# ASCII_Keyboard.net
KiCad netlist of a schematic drawn in Altium Designer
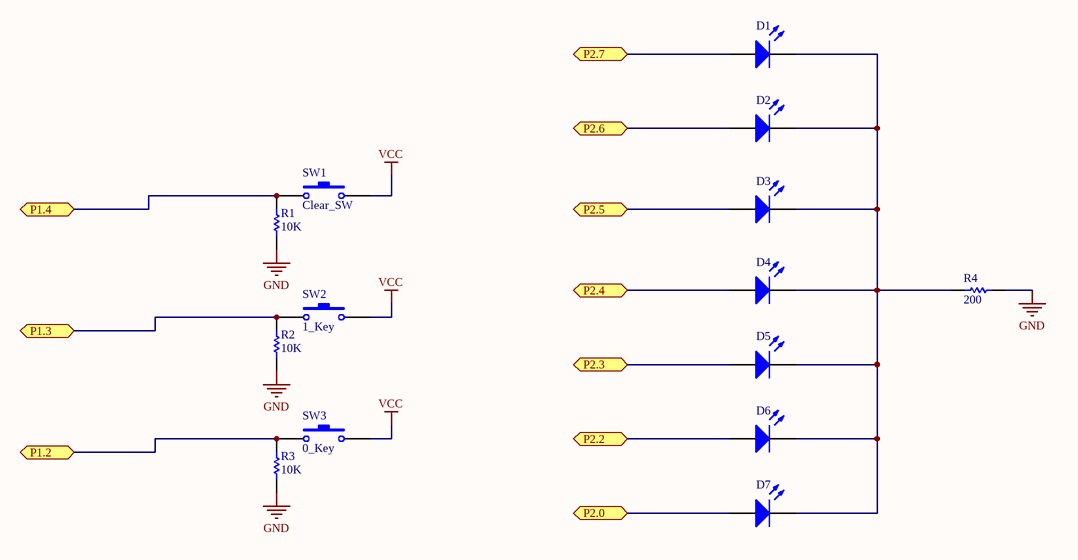
[diagram p0: ASCII_Keyboard.SchDoc]

(export (version "E")
  (design (tool "Eeschema 10.0.6"))
  (components
    (comp (ref "D1")
      (value "LED0")
      (footprint "LED-0")
      (description "Typical INFRARED GaAs LED")
      (fields (field (name "PUBLISHER") "Altium Limited"))
      (libsource (lib "Miscellaneous Devices") (part "LED0"))
    )
    (comp (ref "D2")
      (value "LED0")
      (footprint "LED-0")
      (description "Typical INFRARED GaAs LED")
      (fields (field (name "PUBLISHER") "Altium Limited"))
      (libsource (lib "Miscellaneous Devices") (part "LED0"))
    )
    (comp (ref "D3")
      (value "LED0")
      (footprint "LED-0")
      (description "Typical INFRARED GaAs LED")
      (fields (field (name "PUBLISHER") "Altium Limited"))
      (libsource (lib "Miscellaneous Devices") (part "LED0"))
    )
    (comp (ref "D4")
      (value "LED0")
      (footprint "LED-0")
      (description "Typical INFRARED GaAs LED")
      (fields (field (name "PUBLISHER") "Altium Limited"))
      (libsource (lib "Miscellaneous Devices") (part "LED0"))
    )
    (comp (ref "D5")
      (value "LED0")
      (footprint "LED-0")
      (description "Typical INFRARED GaAs LED")
      (fields (field (name "PUBLISHER") "Altium Limited"))
      (libsource (lib "Miscellaneous Devices") (part "LED0"))
    )
    (comp (ref "D6")
      (value "LED0")
      (footprint "LED-0")
      (description "Typical INFRARED GaAs LED")
      (fields (field (name "PUBLISHER") "Altium Limited"))
      (libsource (lib "Miscellaneous Devices") (part "LED0"))
    )
    (comp (ref "D7")
      (value "LED0")
      (footprint "LED-0")
      (description "Typical INFRARED GaAs LED")
      (fields (field (name "PUBLISHER") "Altium Limited"))
      (libsource (lib "Miscellaneous Devices") (part "LED0"))
    )
    (comp (ref "R1")
      (value "10K")
      (footprint "AXIAL-0.3")
      (description "Resistor")
      (fields (field (name "Comment") "Res1") (field (name "PUBLISHER") "Altium Limited"))
      (libsource (lib "Miscellaneous Devices") (part "Res1"))
    )
    (comp (ref "R2")
      (value "10K")
      (footprint "AXIAL-0.3")
      (description "Resistor")
      (fields (field (name "Comment") "Res1") (field (name "PUBLISHER") "Altium Limited"))
      (libsource (lib "Miscellaneous Devices") (part "Res1"))
    )
    (comp (ref "R3")
      (value "10K")
      (footprint "AXIAL-0.3")
      (description "Resistor")
      (fields (field (name "Comment") "Res1") (field (name "PUBLISHER") "Altium Limited"))
      (libsource (lib "Miscellaneous Devices") (part "Res1"))
    )
    (comp (ref "R4")
      (value "200")
      (footprint "AXIAL-0.3")
      (description "Resistor")
      (fields (field (name "Comment") "Res1") (field (name "PUBLISHER") "Altium Limited"))
      (libsource (lib "Miscellaneous Devices") (part "Res1"))
    )
    (comp (ref "SW1")
      (value "Clear_SW")
      (footprint "SPST-2")
      (description "Switch")
      (fields (field (name "PUBLISHER") "Altium Limited"))
      (libsource (lib "Miscellaneous Devices") (part "SW-PB"))
    )
    (comp (ref "SW2")
      (value "1_Key")
      (footprint "SPST-2")
      (description "Switch")
      (fields (field (name "PUBLISHER") "Altium Limited"))
      (libsource (lib "Miscellaneous Devices") (part "SW-PB"))
    )
    (comp (ref "SW3")
      (value "0_Key")
      (footprint "SPST-2")
      (description "Switch")
      (fields (field (name "PUBLISHER") "Altium Limited"))
      (libsource (lib "Miscellaneous Devices") (part "SW-PB"))
    )
  )
  (nets
    (net (code "1") (name "/P1.2") (class "Default")
      (node (ref "R3") (pin "1") (pinfunction "1_1") (pintype "passive"))
      (node (ref "SW3") (pin "1") (pinfunction "1_1") (pintype "passive"))
    )
    (net (code "2") (name "/P1.3") (class "Default")
      (node (ref "R2") (pin "1") (pinfunction "1_1") (pintype "passive"))
      (node (ref "SW2") (pin "1") (pinfunction "1_1") (pintype "passive"))
    )
    (net (code "3") (name "/P1.4") (class "Default")
      (node (ref "R1") (pin "1") (pinfunction "1_1") (pintype "passive"))
      (node (ref "SW1") (pin "1") (pinfunction "1_1") (pintype "passive"))
    )
    (net (code "4") (name "/P2.0") (class "Default")
      (node (ref "D7") (pin "1") (pinfunction "A_1") (pintype "passive"))
    )
    (net (code "5") (name "/P2.2") (class "Default")
      (node (ref "D6") (pin "1") (pinfunction "A_1") (pintype "passive"))
    )
    (net (code "6") (name "/P2.3") (class "Default")
      (node (ref "D5") (pin "1") (pinfunction "A_1") (pintype "passive"))
    )
    (net (code "7") (name "/P2.4") (class "Default")
      (node (ref "D4") (pin "1") (pinfunction "A_1") (pintype "passive"))
    )
    (net (code "8") (name "/P2.5") (class "Default")
      (node (ref "D3") (pin "1") (pinfunction "A_1") (pintype "passive"))
    )
    (net (code "9") (name "/P2.6") (class "Default")
      (node (ref "D2") (pin "1") (pinfunction "A_1") (pintype "passive"))
    )
    (net (code "10") (name "/P2.7") (class "Default")
      (node (ref "D1") (pin "1") (pinfunction "A_1") (pintype "passive"))
    )
    (net (code "11") (name "GND") (class "Default")
      (node (ref "R1") (pin "2") (pinfunction "2_2") (pintype "passive"))
      (node (ref "R2") (pin "2") (pinfunction "2_2") (pintype "passive"))
      (node (ref "R3") (pin "2") (pinfunction "2_2") (pintype "passive"))
      (node (ref "R4") (pin "2") (pinfunction "2_2") (pintype "passive"))
    )
    (net (code "12") (name "Net-(D1-K)") (class "Default")
      (node (ref "D1") (pin "2") (pinfunction "K_2") (pintype "passive"))
      (node (ref "D2") (pin "2") (pinfunction "K_2") (pintype "passive"))
      (node (ref "D3") (pin "2") (pinfunction "K_2") (pintype "passive"))
      (node (ref "D4") (pin "2") (pinfunction "K_2") (pintype "passive"))
      (node (ref "D5") (pin "2") (pinfunction "K_2") (pintype "passive"))
      (node (ref "D6") (pin "2") (pinfunction "K_2") (pintype "passive"))
      (node (ref "D7") (pin "2") (pinfunction "K_2") (pintype "passive"))
      (node (ref "R4") (pin "1") (pinfunction "1_1") (pintype "passive"))
    )
    (net (code "13") (name "VCC") (class "Default")
      (node (ref "SW1") (pin "2") (pinfunction "2_2") (pintype "passive"))
      (node (ref "SW2") (pin "2") (pinfunction "2_2") (pintype "passive"))
      (node (ref "SW3") (pin "2") (pinfunction "2_2") (pintype "passive"))
    )
  )
)
